# sunrise.net
KiCad netlist of a schematic drawn in EAGLE
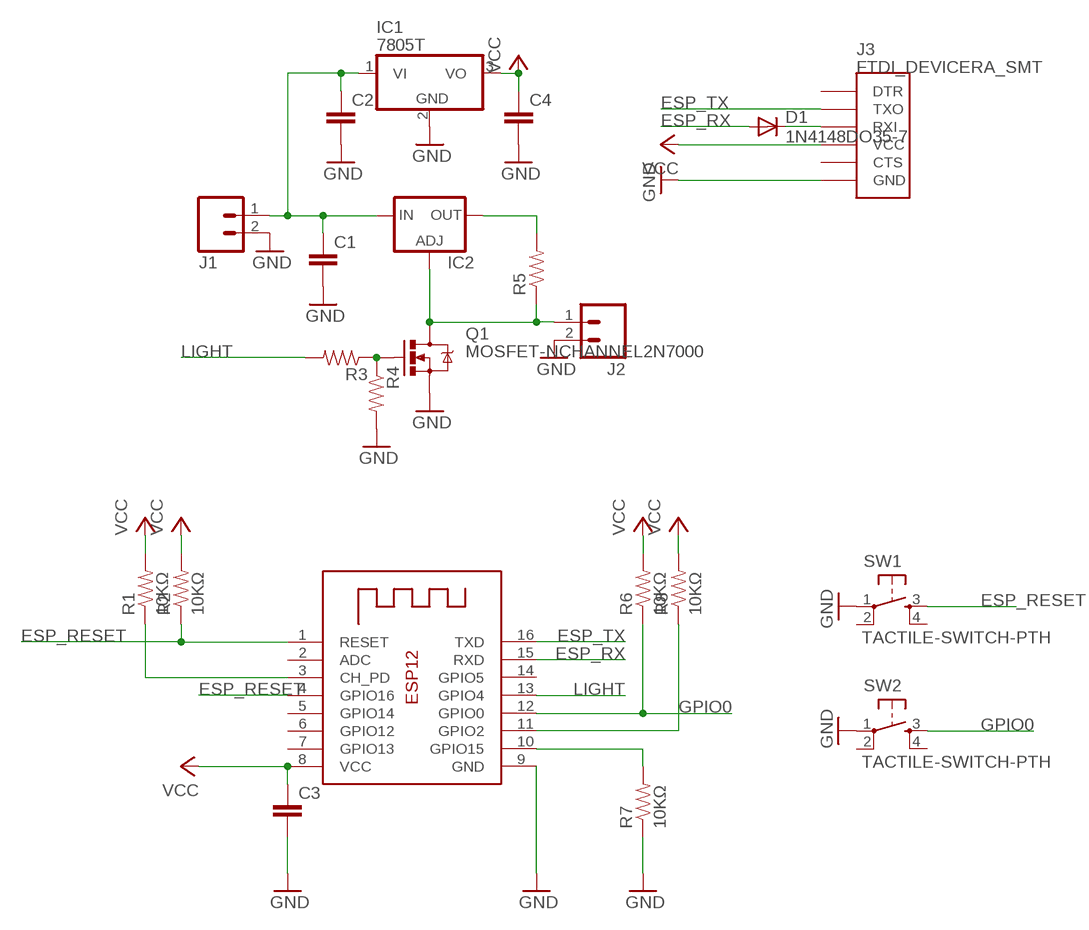
[diagram p0: schematic, sheet 1]

(export (version "E")
  (design (tool "Eeschema 10.0.6"))
  (components
    (comp (ref "C1")
      (value "0.1UF-50V-20%(PTH)KIT-EZ")
      (footprint "eagle-import:CAP-PTH-SMALL-KIT")
      (libsource (lib "eagle-import") (part "0.1UF-50V-20%(PTH)KIT-EZ"))
    )
    (comp (ref "C2")
      (value "0.1UF-50V-20%(PTH)KIT-EZ")
      (footprint "eagle-import:CAP-PTH-SMALL-KIT")
      (libsource (lib "eagle-import") (part "0.1UF-50V-20%(PTH)KIT-EZ"))
    )
    (comp (ref "C3")
      (value "0.1UF-50V-20%(PTH)KIT-EZ")
      (footprint "eagle-import:CAP-PTH-SMALL-KIT")
      (libsource (lib "eagle-import") (part "0.1UF-50V-20%(PTH)KIT-EZ"))
    )
    (comp (ref "C4")
      (value "0.1UF-50V-20%(PTH)KIT-EZ")
      (footprint "eagle-import:CAP-PTH-SMALL-KIT")
      (libsource (lib "eagle-import") (part "0.1UF-50V-20%(PTH)KIT-EZ"))
    )
    (comp (ref "D1")
      (value "1N4148DO35-7")
      (footprint "eagle-import:DO35-7")
      (libsource (lib "eagle-import") (part "1N4148DO35-7"))
    )
    (comp (ref "IC1")
      (value "7805T")
      (footprint "eagle-import:TO220H")
      (libsource (lib "eagle-import") (part "78T05"))
    )
    (comp (ref "IC2")
      (value "LM317-TO3")
      (footprint "eagle-import:TO3-K02")
      (libsource (lib "eagle-import") (part "LM317-TO3"))
    )
    (comp (ref "J1")
      (value "M02LOCK_LONGPADS")
      (footprint "eagle-import:1X02_LOCK_LONGPADS")
      (libsource (lib "eagle-import") (part "M02LOCK_LONGPADS"))
    )
    (comp (ref "J2")
      (value "M02LOCK_LONGPADS")
      (footprint "eagle-import:1X02_LOCK_LONGPADS")
      (libsource (lib "eagle-import") (part "M02LOCK_LONGPADS"))
    )
    (comp (ref "J3")
      (value "FTDI_DEVICERA_SMT")
      (footprint "eagle-import:FTDI_DEVICE_RA_SMT")
      (libsource (lib "eagle-import") (part "FTDI_DEVICERA_SMT"))
    )
    (comp (ref "Q1")
      (value "MOSFET-NCHANNEL2N7000")
      (footprint "eagle-import:TO-92")
      (libsource (lib "eagle-import") (part "MOSFET-NCHANNEL2N7000"))
    )
    (comp (ref "R1")
      (value "10KΩ")
      (footprint "eagle-import:AXIAL-0.4")
      (libsource (lib "eagle-import") (part "RESISTORPTH-1/4W"))
    )
    (comp (ref "R2")
      (value "10KΩ")
      (footprint "eagle-import:AXIAL-0.4")
      (libsource (lib "eagle-import") (part "RESISTORPTH-1/4W"))
    )
    (comp (ref "R3")
      (value "RESISTORPTH-1/4W")
      (footprint "eagle-import:AXIAL-0.4")
      (libsource (lib "eagle-import") (part "RESISTORPTH-1/4W"))
    )
    (comp (ref "R4")
      (value "RESISTORPTH-1/4W")
      (footprint "eagle-import:AXIAL-0.4")
      (libsource (lib "eagle-import") (part "RESISTORPTH-1/4W"))
    )
    (comp (ref "R5")
      (value "RESISTORPTH-1W")
      (footprint "eagle-import:AXIAL-0.6")
      (libsource (lib "eagle-import") (part "RESISTORPTH-1W"))
    )
    (comp (ref "R6")
      (value "10KΩ")
      (footprint "eagle-import:AXIAL-0.4")
      (libsource (lib "eagle-import") (part "RESISTORPTH-1/4W"))
    )
    (comp (ref "R7")
      (value "10KΩ")
      (footprint "eagle-import:AXIAL-0.4")
      (libsource (lib "eagle-import") (part "RESISTORPTH-1/4W"))
    )
    (comp (ref "R8")
      (value "10KΩ")
      (footprint "eagle-import:AXIAL-0.4")
      (libsource (lib "eagle-import") (part "RESISTORPTH-1/4W"))
    )
    (comp (ref "SW1")
      (value "TACTILE-SWITCH-PTH")
      (footprint "eagle-import:TAC-SWITCH-PTH")
      (libsource (lib "eagle-import") (part "TACTILE-SWITCH-PTH"))
    )
    (comp (ref "SW2")
      (value "TACTILE-SWITCH-PTH")
      (footprint "eagle-import:TAC-SWITCH-PTH")
      (libsource (lib "eagle-import") (part "TACTILE-SWITCH-PTH"))
    )
    (comp (ref "X1")
      (value "ESP-12e")
      (footprint "eagle-import:ESP-12")
      (libsource (lib "eagle-import") (part "ESP-12"))
    )
  )
  (nets
    (net (code "1") (name "/ESP_RESET") (class "Default")
      (node (ref "R2") (pin "P$1") (pinfunction "1_P$1") (pintype "passive"))
      (node (ref "SW1") (pin "3") (pinfunction "3_3") (pintype "passive"))
      (node (ref "X1") (pin "1") (pinfunction "RESET_1") (pintype "input"))
      (node (ref "X1") (pin "4") (pinfunction "GPIO16_4") (pintype "bidirectional"))
    )
    (net (code "2") (name "/ESP_RX") (class "Default")
      (node (ref "D1") (pin "A") (pinfunction "A_A") (pintype "passive"))
      (node (ref "X1") (pin "15") (pinfunction "RXD_15") (pintype "input"))
    )
    (net (code "3") (name "/ESP_TX") (class "Default")
      (node (ref "J3") (pin "2") (pinfunction "TXO_2") (pintype "bidirectional"))
      (node (ref "X1") (pin "16") (pinfunction "TXD_16") (pintype "output"))
    )
    (net (code "4") (name "/GPIO0") (class "Default")
      (node (ref "R6") (pin "P$1") (pinfunction "1_P$1") (pintype "passive"))
      (node (ref "SW2") (pin "3") (pinfunction "3_3") (pintype "passive"))
      (node (ref "X1") (pin "12") (pinfunction "GPIO0_12") (pintype "bidirectional"))
    )
    (net (code "5") (name "/LIGHT") (class "Default")
      (node (ref "R3") (pin "P$2") (pinfunction "2_P$2") (pintype "passive"))
      (node (ref "X1") (pin "13") (pinfunction "GPIO4_13") (pintype "bidirectional"))
    )
    (net (code "6") (name "GND") (class "Default")
      (node (ref "C1") (pin "2") (pinfunction "2_2") (pintype "passive"))
      (node (ref "C2") (pin "2") (pinfunction "2_2") (pintype "passive"))
      (node (ref "C3") (pin "2") (pinfunction "2_2") (pintype "passive"))
      (node (ref "C4") (pin "2") (pinfunction "2_2") (pintype "passive"))
      (node (ref "IC1") (pin "2") (pinfunction "GND_2") (pintype "passive"))
      (node (ref "J1") (pin "2") (pinfunction "2_2") (pintype "passive"))
      (node (ref "J2") (pin "2") (pinfunction "2_2") (pintype "passive"))
      (node (ref "J3") (pin "6") (pinfunction "GND_6") (pintype "bidirectional"))
      (node (ref "Q1") (pin "1") (pinfunction "S_1") (pintype "passive"))
      (node (ref "R4") (pin "P$2") (pinfunction "2_P$2") (pintype "passive"))
      (node (ref "R7") (pin "P$1") (pinfunction "1_P$1") (pintype "passive"))
      (node (ref "SW1") (pin "1") (pinfunction "1_1") (pintype "passive"))
      (node (ref "SW2") (pin "1") (pinfunction "1_1") (pintype "passive"))
      (node (ref "X1") (pin "9") (pinfunction "GND_9") (pintype "power_in"))
    )
    (net (code "7") (name "Net-(IC1-VI)") (class "Default")
      (node (ref "C1") (pin "1") (pinfunction "1_1") (pintype "passive"))
      (node (ref "C2") (pin "1") (pinfunction "1_1") (pintype "passive"))
      (node (ref "IC1") (pin "1") (pinfunction "VI_1") (pintype "input"))
      (node (ref "IC2") (pin "1") (pinfunction "IN_1") (pintype "input"))
      (node (ref "J1") (pin "1") (pinfunction "1_1") (pintype "passive"))
    )
    (net (code "8") (name "Net-(IC2-ADJ)") (class "Default")
      (node (ref "IC2") (pin "2") (pinfunction "ADJ_2") (pintype "input"))
      (node (ref "J2") (pin "1") (pinfunction "1_1") (pintype "passive"))
      (node (ref "Q1") (pin "3") (pinfunction "D_3") (pintype "passive"))
      (node (ref "R5") (pin "P$1") (pinfunction "1_P$1") (pintype "passive"))
    )
    (net (code "9") (name "Net-(IC2-OUT)") (class "Default")
      (node (ref "IC2") (pin "3") (pinfunction "OUT_3") (pintype "passive"))
      (node (ref "R5") (pin "P$2") (pinfunction "2_P$2") (pintype "passive"))
    )
    (net (code "10") (name "Net-(J3-RXI)") (class "Default")
      (node (ref "D1") (pin "C") (pinfunction "C_C") (pintype "passive"))
      (node (ref "J3") (pin "3") (pinfunction "RXI_3") (pintype "bidirectional"))
    )
    (net (code "11") (name "Net-(Q1-G)") (class "Default")
      (node (ref "Q1") (pin "2") (pinfunction "G_2") (pintype "passive"))
      (node (ref "R3") (pin "P$1") (pinfunction "1_P$1") (pintype "passive"))
      (node (ref "R4") (pin "P$1") (pinfunction "1_P$1") (pintype "passive"))
    )
    (net (code "12") (name "Net-(R1-1)") (class "Default")
      (node (ref "R1") (pin "P$1") (pinfunction "1_P$1") (pintype "passive"))
      (node (ref "X1") (pin "3") (pinfunction "CH_PD_3") (pintype "input"))
    )
    (net (code "13") (name "Net-(R7-2)") (class "Default")
      (node (ref "R7") (pin "P$2") (pinfunction "2_P$2") (pintype "passive"))
      (node (ref "X1") (pin "10") (pinfunction "GPIO15_10") (pintype "bidirectional"))
    )
    (net (code "14") (name "Net-(R8-1)") (class "Default")
      (node (ref "R8") (pin "P$1") (pinfunction "1_P$1") (pintype "passive"))
      (node (ref "X1") (pin "11") (pinfunction "GPIO2_11") (pintype "bidirectional"))
    )
    (net (code "15") (name "VCC") (class "Default")
      (node (ref "C3") (pin "1") (pinfunction "1_1") (pintype "passive"))
      (node (ref "C4") (pin "1") (pinfunction "1_1") (pintype "passive"))
      (node (ref "IC1") (pin "3") (pinfunction "VO_3") (pintype "passive"))
      (node (ref "J3") (pin "4") (pinfunction "VCC_4") (pintype "bidirectional"))
      (node (ref "R1") (pin "P$2") (pinfunction "2_P$2") (pintype "passive"))
      (node (ref "R2") (pin "P$2") (pinfunction "2_P$2") (pintype "passive"))
      (node (ref "R6") (pin "P$2") (pinfunction "2_P$2") (pintype "passive"))
      (node (ref "R8") (pin "P$2") (pinfunction "2_P$2") (pintype "passive"))
      (node (ref "X1") (pin "8") (pinfunction "VCC_8") (pintype "power_in"))
    )
    (net (code "16") (name "unconnected-(J3-CTS-Pad5)") (class "Default")
      (node (ref "J3") (pin "5") (pinfunction "CTS_5") (pintype "bidirectional"))
    )
    (net (code "17") (name "unconnected-(J3-DTR-Pad1)") (class "Default")
      (node (ref "J3") (pin "1") (pinfunction "DTR_1") (pintype "bidirectional"))
    )
    (net (code "18") (name "unconnected-(SW1-Pad2)") (class "Default")
      (node (ref "SW1") (pin "2") (pinfunction "2_2") (pintype "passive"))
    )
    (net (code "19") (name "unconnected-(SW1-Pad4)") (class "Default")
      (node (ref "SW1") (pin "4") (pinfunction "4_4") (pintype "passive"))
    )
    (net (code "20") (name "unconnected-(SW2-Pad2)") (class "Default")
      (node (ref "SW2") (pin "2") (pinfunction "2_2") (pintype "passive"))
    )
    (net (code "21") (name "unconnected-(SW2-Pad4)") (class "Default")
      (node (ref "SW2") (pin "4") (pinfunction "4_4") (pintype "passive"))
    )
    (net (code "22") (name "unconnected-(X1-ADC-Pad2)") (class "Default")
      (node (ref "X1") (pin "2") (pinfunction "ADC_2") (pintype "passive"))
    )
    (net (code "23") (name "unconnected-(X1-GPIO5-Pad14)") (class "Default")
      (node (ref "X1") (pin "14") (pinfunction "GPIO5_14") (pintype "bidirectional"))
    )
    (net (code "24") (name "unconnected-(X1-GPIO12-Pad6)") (class "Default")
      (node (ref "X1") (pin "6") (pinfunction "GPIO12_6") (pintype "bidirectional"))
    )
    (net (code "25") (name "unconnected-(X1-GPIO13-Pad7)") (class "Default")
      (node (ref "X1") (pin "7") (pinfunction "GPIO13_7") (pintype "bidirectional"))
    )
    (net (code "26") (name "unconnected-(X1-GPIO14-Pad5)") (class "Default")
      (node (ref "X1") (pin "5") (pinfunction "GPIO14_5") (pintype "bidirectional"))
    )
  )
)
